# Sheet.net
KiCad netlist of a schematic drawn in Altium Designer
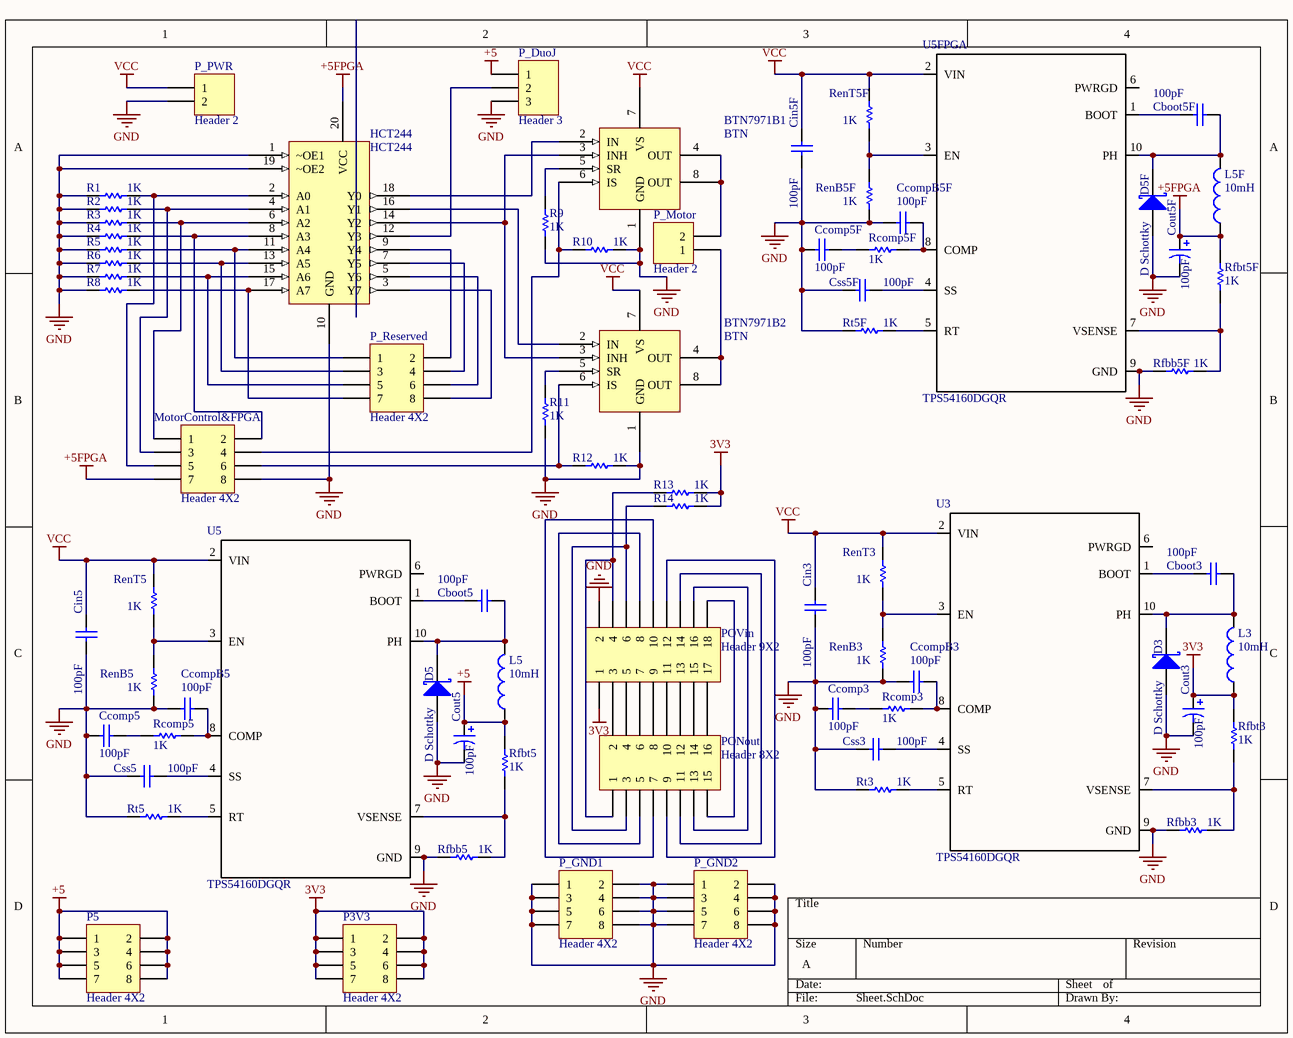
[diagram p0: Sheet.SchDoc]

(export (version "E")
  (design (tool "Eeschema 10.0.6"))
  (components
    (comp (ref "BTN7971B1")
      (value "BTN")
      (footprint "BTN7971B")
      (libsource (lib "2017-07-30_02-04-41") (part "BTN"))
    )
    (comp (ref "BTN7971B2")
      (value "BTN")
      (footprint "BTN7971B")
      (libsource (lib "2017-07-30_02-04-41") (part "BTN"))
    )
    (comp (ref "Cboot3")
      (value "100pF")
      (footprint "RAD-0.3")
      (description "Capacitor")
      (fields (field (name "Comment") "Cap") (field (name "PUBLISHER") "Altium Limited"))
      (libsource (lib "Miscellaneous Devices") (part "Cap"))
    )
    (comp (ref "Cboot5")
      (value "100pF")
      (footprint "RAD-0.3")
      (description "Capacitor")
      (fields (field (name "Comment") "Cap") (field (name "PUBLISHER") "Altium Limited"))
      (libsource (lib "Miscellaneous Devices") (part "Cap"))
    )
    (comp (ref "Cboot5F")
      (value "100pF")
      (footprint "RAD-0.3")
      (description "Capacitor")
      (fields (field (name "Comment") "Cap") (field (name "PUBLISHER") "Altium Limited"))
      (libsource (lib "Miscellaneous Devices") (part "Cap"))
    )
    (comp (ref "Ccomp3")
      (value "100pF")
      (footprint "RAD-0.3")
      (description "Capacitor")
      (fields (field (name "Comment") "Cap") (field (name "PUBLISHER") "Altium Limited"))
      (libsource (lib "Miscellaneous Devices") (part "Cap"))
    )
    (comp (ref "Ccomp5")
      (value "100pF")
      (footprint "RAD-0.3")
      (description "Capacitor")
      (fields (field (name "Comment") "Cap") (field (name "PUBLISHER") "Altium Limited"))
      (libsource (lib "Miscellaneous Devices") (part "Cap"))
    )
    (comp (ref "Ccomp5F")
      (value "100pF")
      (footprint "RAD-0.3")
      (description "Capacitor")
      (fields (field (name "Comment") "Cap") (field (name "PUBLISHER") "Altium Limited"))
      (libsource (lib "Miscellaneous Devices") (part "Cap"))
    )
    (comp (ref "CcompB3")
      (value "100pF")
      (footprint "RAD-0.3")
      (description "Capacitor")
      (fields (field (name "Comment") "Cap") (field (name "PUBLISHER") "Altium Limited"))
      (libsource (lib "Miscellaneous Devices") (part "Cap"))
    )
    (comp (ref "CcompB5")
      (value "100pF")
      (footprint "RAD-0.3")
      (description "Capacitor")
      (fields (field (name "Comment") "Cap") (field (name "PUBLISHER") "Altium Limited"))
      (libsource (lib "Miscellaneous Devices") (part "Cap"))
    )
    (comp (ref "CcompB5F")
      (value "100pF")
      (footprint "RAD-0.3")
      (description "Capacitor")
      (fields (field (name "Comment") "Cap") (field (name "PUBLISHER") "Altium Limited"))
      (libsource (lib "Miscellaneous Devices") (part "Cap"))
    )
    (comp (ref "Cin3")
      (value "100pF")
      (footprint "RAD-0.3")
      (description "Capacitor")
      (fields (field (name "Comment") "Cap") (field (name "PUBLISHER") "Altium Limited"))
      (libsource (lib "Miscellaneous Devices") (part "Cap"))
    )
    (comp (ref "Cin5")
      (value "100pF")
      (footprint "RAD-0.3")
      (description "Capacitor")
      (fields (field (name "Comment") "Cap") (field (name "PUBLISHER") "Altium Limited"))
      (libsource (lib "Miscellaneous Devices") (part "Cap"))
    )
    (comp (ref "Cin5F")
      (value "100pF")
      (footprint "RAD-0.3")
      (description "Capacitor")
      (fields (field (name "Comment") "Cap") (field (name "PUBLISHER") "Altium Limited"))
      (libsource (lib "Miscellaneous Devices") (part "Cap"))
    )
    (comp (ref "Cout3")
      (value "100pF")
      (footprint "RB7.6-15")
      (description "Polarized Capacitor (Radial)")
      (fields (field (name "Comment") "Cap Pol1") (field (name "PUBLISHER") "Altium Limited"))
      (libsource (lib "Miscellaneous Devices") (part "Cap Pol1"))
    )
    (comp (ref "Cout5")
      (value "100pF")
      (footprint "RB7.6-15")
      (description "Polarized Capacitor (Radial)")
      (fields (field (name "Comment") "Cap Pol1") (field (name "PUBLISHER") "Altium Limited"))
      (libsource (lib "Miscellaneous Devices") (part "Cap Pol1"))
    )
    (comp (ref "Cout5F")
      (value "100pF")
      (footprint "RB7.6-15")
      (description "Polarized Capacitor (Radial)")
      (fields (field (name "Comment") "Cap Pol1") (field (name "PUBLISHER") "Altium Limited"))
      (libsource (lib "Miscellaneous Devices") (part "Cap Pol1"))
    )
    (comp (ref "Css3")
      (value "100pF")
      (footprint "RAD-0.3")
      (description "Capacitor")
      (fields (field (name "Comment") "Cap") (field (name "PUBLISHER") "Altium Limited"))
      (libsource (lib "Miscellaneous Devices") (part "Cap"))
    )
    (comp (ref "Css5")
      (value "100pF")
      (footprint "RAD-0.3")
      (description "Capacitor")
      (fields (field (name "Comment") "Cap") (field (name "PUBLISHER") "Altium Limited"))
      (libsource (lib "Miscellaneous Devices") (part "Cap"))
    )
    (comp (ref "Css5F")
      (value "100pF")
      (footprint "RAD-0.3")
      (description "Capacitor")
      (fields (field (name "Comment") "Cap") (field (name "PUBLISHER") "Altium Limited"))
      (libsource (lib "Miscellaneous Devices") (part "Cap"))
    )
    (comp (ref "D3")
      (value "D Schottky")
      (footprint "SMB")
      (description "Schottky Diode")
      (fields (field (name "PUBLISHER") "Altium Limited"))
      (libsource (lib "Miscellaneous Devices") (part "D Schottky"))
    )
    (comp (ref "D5")
      (value "D Schottky")
      (footprint "SMB")
      (description "Schottky Diode")
      (fields (field (name "PUBLISHER") "Altium Limited"))
      (libsource (lib "Miscellaneous Devices") (part "D Schottky"))
    )
    (comp (ref "D5F")
      (value "D Schottky")
      (footprint "SMB")
      (description "Schottky Diode")
      (fields (field (name "PUBLISHER") "Altium Limited"))
      (libsource (lib "Miscellaneous Devices") (part "D Schottky"))
    )
    (comp (ref "HCT244")
      (value "HCT244")
      (footprint "DIP20")
      (libsource (lib "2017-07-30_02-04-41") (part "HCT244"))
    )
    (comp (ref "L3")
      (value "10mH")
      (footprint "0805")
      (description "Inductor")
      (fields (field (name "PUBLISHER") "Altium Limited"))
      (libsource (lib "Miscellaneous Devices") (part "Inductor"))
    )
    (comp (ref "L5")
      (value "10mH")
      (footprint "0805")
      (description "Inductor")
      (fields (field (name "PUBLISHER") "Altium Limited"))
      (libsource (lib "Miscellaneous Devices") (part "Inductor"))
    )
    (comp (ref "L5F")
      (value "10mH")
      (footprint "0805")
      (description "Inductor")
      (fields (field (name "PUBLISHER") "Altium Limited"))
      (libsource (lib "Miscellaneous Devices") (part "Inductor"))
    )
    (comp (ref "MotorControl&FPGA")
      (value "Header 4X2")
      (footprint "HDR2X4")
      (description "Header, 4-Pin, Dual row")
      (fields (field (name "PUBLISHER") "Altium Limited"))
      (libsource (lib "Miscellaneous Connectors") (part "Header 4X2"))
    )
    (comp (ref "P3V3")
      (value "Header 4X2")
      (footprint "HDR2X4")
      (description "Header, 4-Pin, Dual row")
      (fields (field (name "PUBLISHER") "Altium Limited"))
      (libsource (lib "Miscellaneous Connectors") (part "Header 4X2"))
    )
    (comp (ref "P5")
      (value "Header 4X2")
      (footprint "HDR2X4")
      (description "Header, 4-Pin, Dual row")
      (fields (field (name "PUBLISHER") "Altium Limited"))
      (libsource (lib "Miscellaneous Connectors") (part "Header 4X2"))
    )
    (comp (ref "PONout")
      (value "Header 8X2")
      (footprint "HDR2X8")
      (description "Header, 8-Pin, Dual row")
      (fields (field (name "PUBLISHER") "Altium Limited"))
      (libsource (lib "Miscellaneous Connectors") (part "Header 8X2"))
    )
    (comp (ref "POVin")
      (value "Header 9X2")
      (footprint "HDR2X9")
      (description "Header, 9-Pin, Dual row")
      (fields (field (name "PUBLISHER") "Altium Limited"))
      (libsource (lib "Miscellaneous Connectors") (part "Header 9X2"))
    )
    (comp (ref "P_DuoJ")
      (value "Header 3")
      (footprint "HDR1X3")
      (description "Header, 3-Pin")
      (fields (field (name "PUBLISHER") "Altium Limited"))
      (libsource (lib "Miscellaneous Connectors") (part "Header 3"))
    )
    (comp (ref "P_GND1")
      (value "Header 4X2")
      (footprint "HDR2X4")
      (description "Header, 4-Pin, Dual row")
      (fields (field (name "PUBLISHER") "Altium Limited"))
      (libsource (lib "Miscellaneous Connectors") (part "Header 4X2"))
    )
    (comp (ref "P_GND2")
      (value "Header 4X2")
      (footprint "HDR2X4")
      (description "Header, 4-Pin, Dual row")
      (fields (field (name "PUBLISHER") "Altium Limited"))
      (libsource (lib "Miscellaneous Connectors") (part "Header 4X2"))
    )
    (comp (ref "P_Motor")
      (value "Header 2")
      (footprint "HDR1X2")
      (description "Header, 2-Pin")
      (fields (field (name "PUBLISHER") "Altium Limited"))
      (libsource (lib "") (part "Header 2_1"))
    )
    (comp (ref "P_PWR")
      (value "Header 2")
      (footprint "HDR1X2")
      (description "Header, 2-Pin")
      (fields (field (name "PUBLISHER") "Altium Limited"))
      (libsource (lib "Miscellaneous Connectors") (part "Header 2"))
    )
    (comp (ref "P_Reserved")
      (value "Header 4X2")
      (footprint "HDR2X4")
      (description "Header, 4-Pin, Dual row")
      (fields (field (name "PUBLISHER") "Altium Limited"))
      (libsource (lib "Miscellaneous Connectors") (part "Header 4X2"))
    )
    (comp (ref "R1")
      (value "1K")
      (footprint "AXIAL-0.3")
      (description "Resistor")
      (fields (field (name "Comment") "Res1") (field (name "PUBLISHER") "Altium Limited"))
      (libsource (lib "Miscellaneous Devices") (part "Res1"))
    )
    (comp (ref "R2")
      (value "1K")
      (footprint "AXIAL-0.3")
      (description "Resistor")
      (fields (field (name "Comment") "Res1") (field (name "PUBLISHER") "Altium Limited"))
      (libsource (lib "Miscellaneous Devices") (part "Res1"))
    )
    (comp (ref "R3")
      (value "1K")
      (footprint "AXIAL-0.3")
      (description "Resistor")
      (fields (field (name "Comment") "Res1") (field (name "PUBLISHER") "Altium Limited"))
      (libsource (lib "Miscellaneous Devices") (part "Res1"))
    )
    (comp (ref "R4")
      (value "1K")
      (footprint "AXIAL-0.3")
      (description "Resistor")
      (fields (field (name "Comment") "Res1") (field (name "PUBLISHER") "Altium Limited"))
      (libsource (lib "Miscellaneous Devices") (part "Res1"))
    )
    (comp (ref "R5")
      (value "1K")
      (footprint "AXIAL-0.3")
      (description "Resistor")
      (fields (field (name "Comment") "Res1") (field (name "PUBLISHER") "Altium Limited"))
      (libsource (lib "Miscellaneous Devices") (part "Res1"))
    )
    (comp (ref "R6")
      (value "1K")
      (footprint "AXIAL-0.3")
      (description "Resistor")
      (fields (field (name "Comment") "Res1") (field (name "PUBLISHER") "Altium Limited"))
      (libsource (lib "Miscellaneous Devices") (part "Res1"))
    )
    (comp (ref "R7")
      (value "1K")
      (footprint "AXIAL-0.3")
      (description "Resistor")
      (fields (field (name "Comment") "Res1") (field (name "PUBLISHER") "Altium Limited"))
      (libsource (lib "Miscellaneous Devices") (part "Res1"))
    )
    (comp (ref "R8")
      (value "1K")
      (footprint "AXIAL-0.3")
      (description "Resistor")
      (fields (field (name "Comment") "Res1") (field (name "PUBLISHER") "Altium Limited"))
      (libsource (lib "Miscellaneous Devices") (part "Res1"))
    )
    (comp (ref "R9")
      (value "1K")
      (footprint "AXIAL-0.3")
      (description "Resistor")
      (fields (field (name "Comment") "Res1") (field (name "PUBLISHER") "Altium Limited"))
      (libsource (lib "Miscellaneous Devices") (part "Res1"))
    )
    (comp (ref "R10")
      (value "1K")
      (footprint "AXIAL-0.3")
      (description "Resistor")
      (fields (field (name "Comment") "Res1") (field (name "PUBLISHER") "Altium Limited"))
      (libsource (lib "Miscellaneous Devices") (part "Res1"))
    )
    (comp (ref "R11")
      (value "1K")
      (footprint "AXIAL-0.3")
      (description "Resistor")
      (fields (field (name "Comment") "Res1") (field (name "PUBLISHER") "Altium Limited"))
      (libsource (lib "Miscellaneous Devices") (part "Res1"))
    )
    (comp (ref "R12")
      (value "1K")
      (footprint "AXIAL-0.3")
      (description "Resistor")
      (fields (field (name "Comment") "Res1") (field (name "PUBLISHER") "Altium Limited"))
      (libsource (lib "Miscellaneous Devices") (part "Res1"))
    )
    (comp (ref "R13")
      (value "1K")
      (footprint "AXIAL-0.3")
      (description "Resistor")
      (fields (field (name "Comment") "Res1") (field (name "PUBLISHER") "Altium Limited"))
      (libsource (lib "Miscellaneous Devices") (part "Res1"))
    )
    (comp (ref "R14")
      (value "1K")
      (footprint "AXIAL-0.3")
      (description "Resistor")
      (fields (field (name "Comment") "Res1") (field (name "PUBLISHER") "Altium Limited"))
      (libsource (lib "Miscellaneous Devices") (part "Res1"))
    )
    (comp (ref "Rcomp3")
      (value "1K")
      (footprint "AXIAL-0.3")
      (description "Resistor")
      (fields (field (name "Comment") "Res1") (field (name "PUBLISHER") "Altium Limited"))
      (libsource (lib "Miscellaneous Devices") (part "Res1"))
    )
    (comp (ref "Rcomp5")
      (value "1K")
      (footprint "AXIAL-0.3")
      (description "Resistor")
      (fields (field (name "Comment") "Res1") (field (name "PUBLISHER") "Altium Limited"))
      (libsource (lib "Miscellaneous Devices") (part "Res1"))
    )
    (comp (ref "Rcomp5F")
      (value "1K")
      (footprint "AXIAL-0.3")
      (description "Resistor")
      (fields (field (name "Comment") "Res1") (field (name "PUBLISHER") "Altium Limited"))
      (libsource (lib "Miscellaneous Devices") (part "Res1"))
    )
    (comp (ref "RenB3")
      (value "1K")
      (footprint "AXIAL-0.3")
      (description "Resistor")
      (fields (field (name "Comment") "Res1") (field (name "PUBLISHER") "Altium Limited"))
      (libsource (lib "Miscellaneous Devices") (part "Res1"))
    )
    (comp (ref "RenB5")
      (value "1K")
      (footprint "AXIAL-0.3")
      (description "Resistor")
      (fields (field (name "Comment") "Res1") (field (name "PUBLISHER") "Altium Limited"))
      (libsource (lib "Miscellaneous Devices") (part "Res1"))
    )
    (comp (ref "RenB5F")
      (value "1K")
      (footprint "AXIAL-0.3")
      (description "Resistor")
      (fields (field (name "Comment") "Res1") (field (name "PUBLISHER") "Altium Limited"))
      (libsource (lib "Miscellaneous Devices") (part "Res1"))
    )
    (comp (ref "RenT3")
      (value "1K")
      (footprint "AXIAL-0.3")
      (description "Resistor")
      (fields (field (name "Comment") "Res1") (field (name "PUBLISHER") "Altium Limited"))
      (libsource (lib "Miscellaneous Devices") (part "Res1"))
    )
    (comp (ref "RenT5")
      (value "1K")
      (footprint "AXIAL-0.3")
      (description "Resistor")
      (fields (field (name "Comment") "Res1") (field (name "PUBLISHER") "Altium Limited"))
      (libsource (lib "Miscellaneous Devices") (part "Res1"))
    )
    (comp (ref "RenT5F")
      (value "1K")
      (footprint "AXIAL-0.3")
      (description "Resistor")
      (fields (field (name "Comment") "Res1") (field (name "PUBLISHER") "Altium Limited"))
      (libsource (lib "Miscellaneous Devices") (part "Res1"))
    )
    (comp (ref "Rfbb3")
      (value "1K")
      (footprint "AXIAL-0.3")
      (description "Resistor")
      (fields (field (name "Comment") "Res1") (field (name "PUBLISHER") "Altium Limited"))
      (libsource (lib "Miscellaneous Devices") (part "Res1"))
    )
    (comp (ref "Rfbb5")
      (value "1K")
      (footprint "AXIAL-0.3")
      (description "Resistor")
      (fields (field (name "Comment") "Res1") (field (name "PUBLISHER") "Altium Limited"))
      (libsource (lib "Miscellaneous Devices") (part "Res1"))
    )
    (comp (ref "Rfbb5F")
      (value "1K")
      (footprint "AXIAL-0.3")
      (description "Resistor")
      (fields (field (name "Comment") "Res1") (field (name "PUBLISHER") "Altium Limited"))
      (libsource (lib "Miscellaneous Devices") (part "Res1"))
    )
    (comp (ref "Rfbt3")
      (value "1K")
      (footprint "AXIAL-0.3")
      (description "Resistor")
      (fields (field (name "Comment") "Res1") (field (name "PUBLISHER") "Altium Limited"))
      (libsource (lib "Miscellaneous Devices") (part "Res1"))
    )
    (comp (ref "Rfbt5")
      (value "1K")
      (footprint "AXIAL-0.3")
      (description "Resistor")
      (fields (field (name "Comment") "Res1") (field (name "PUBLISHER") "Altium Limited"))
      (libsource (lib "Miscellaneous Devices") (part "Res1"))
    )
    (comp (ref "Rfbt5F")
      (value "1K")
      (footprint "AXIAL-0.3")
      (description "Resistor")
      (fields (field (name "Comment") "Res1") (field (name "PUBLISHER") "Altium Limited"))
      (libsource (lib "Miscellaneous Devices") (part "Res1"))
    )
    (comp (ref "Rt3")
      (value "1K")
      (footprint "AXIAL-0.3")
      (description "Resistor")
      (fields (field (name "Comment") "Res1") (field (name "PUBLISHER") "Altium Limited"))
      (libsource (lib "Miscellaneous Devices") (part "Res1"))
    )
    (comp (ref "Rt5")
      (value "1K")
      (footprint "AXIAL-0.3")
      (description "Resistor")
      (fields (field (name "Comment") "Res1") (field (name "PUBLISHER") "Altium Limited"))
      (libsource (lib "Miscellaneous Devices") (part "Res1"))
    )
    (comp (ref "Rt5F")
      (value "1K")
      (footprint "AXIAL-0.3")
      (description "Resistor")
      (fields (field (name "Comment") "Res1") (field (name "PUBLISHER") "Altium Limited"))
      (libsource (lib "Miscellaneous Devices") (part "Res1"))
    )
    (comp (ref "U3")
      (value "TPS54160DGQR")
      (footprint "S-PDSO-G10")
      (description "Imported")
      (fields (field (name "MANUFACTURER_PART_NUMBER") "TPS54140DGQR"))
      (libsource (lib "2017-07-30_02-04-41") (part "TPS54160DGQR"))
    )
    (comp (ref "U5")
      (value "TPS54160DGQR")
      (footprint "S-PDSO-G10")
      (description "Imported")
      (fields (field (name "MANUFACTURER_PART_NUMBER") "TPS54140DGQR"))
      (libsource (lib "2017-07-30_02-04-41") (part "TPS54160DGQR"))
    )
    (comp (ref "U5FPGA")
      (value "TPS54160DGQR")
      (footprint "S-PDSO-G10")
      (description "Imported")
      (fields (field (name "MANUFACTURER_PART_NUMBER") "TPS54140DGQR"))
      (libsource (lib "2017-07-30_02-04-41") (part "TPS54160DGQR"))
    )
  )
  (nets
    (net (code "1") (name "+5") (class "Default")
      (node (ref "Cout5") (pin "1") (pinfunction "1_1") (pintype "passive"))
      (node (ref "L5") (pin "1") (pinfunction "1_1") (pintype "passive"))
      (node (ref "P5") (pin "1") (pinfunction "1_1") (pintype "passive"))
      (node (ref "P5") (pin "2") (pinfunction "2_2") (pintype "passive"))
      (node (ref "P5") (pin "3") (pinfunction "3_3") (pintype "passive"))
      (node (ref "P5") (pin "4") (pinfunction "4_4") (pintype "passive"))
      (node (ref "P5") (pin "5") (pinfunction "5_5") (pintype "passive"))
      (node (ref "P5") (pin "6") (pinfunction "6_6") (pintype "passive"))
      (node (ref "P5") (pin "7") (pinfunction "7_7") (pintype "passive"))
      (node (ref "P5") (pin "8") (pinfunction "8_8") (pintype "passive"))
      (node (ref "P_DuoJ") (pin "1") (pinfunction "1_1") (pintype "passive"))
      (node (ref "Rfbt5") (pin "2") (pinfunction "2_2") (pintype "passive"))
    )
    (net (code "2") (name "+5FPGA") (class "Default")
      (node (ref "Cout5F") (pin "1") (pinfunction "1_1") (pintype "passive"))
      (node (ref "HCT244") (pin "20") (pinfunction "VCC_20") (pintype "power_in"))
      (node (ref "L5F") (pin "1") (pinfunction "1_1") (pintype "passive"))
      (node (ref "MotorControl&FPGA") (pin "7") (pinfunction "7_7") (pintype "passive"))
      (node (ref "Rfbt5F") (pin "2") (pinfunction "2_2") (pintype "passive"))
    )
    (net (code "3") (name "3V3") (class "Default")
      (node (ref "Cout3") (pin "1") (pinfunction "1_1") (pintype "passive"))
      (node (ref "L3") (pin "1") (pinfunction "1_1") (pintype "passive"))
      (node (ref "P3V3") (pin "1") (pinfunction "1_1") (pintype "passive"))
      (node (ref "P3V3") (pin "2") (pinfunction "2_2") (pintype "passive"))
      (node (ref "P3V3") (pin "3") (pinfunction "3_3") (pintype "passive"))
      (node (ref "P3V3") (pin "4") (pinfunction "4_4") (pintype "passive"))
      (node (ref "P3V3") (pin "5") (pinfunction "5_5") (pintype "passive"))
      (node (ref "P3V3") (pin "6") (pinfunction "6_6") (pintype "passive"))
      (node (ref "P3V3") (pin "7") (pinfunction "7_7") (pintype "passive"))
      (node (ref "P3V3") (pin "8") (pinfunction "8_8") (pintype "passive"))
      (node (ref "POVin") (pin "1") (pinfunction "1_1") (pintype "passive"))
      (node (ref "R13") (pin "2") (pinfunction "2_2") (pintype "passive"))
      (node (ref "R14") (pin "2") (pinfunction "2_2") (pintype "passive"))
      (node (ref "Rfbt3") (pin "2") (pinfunction "2_2") (pintype "passive"))
    )
    (net (code "4") (name "GND") (class "Default")
      (node (ref "BTN7971B1") (pin "1") (pinfunction "GND_1") (pintype "power_in"))
      (node (ref "BTN7971B2") (pin "1") (pinfunction "GND_1") (pintype "power_in"))
      (node (ref "Ccomp3") (pin "2") (pinfunction "2_2") (pintype "passive"))
      (node (ref "Ccomp5") (pin "2") (pinfunction "2_2") (pintype "passive"))
      (node (ref "Ccomp5F") (pin "2") (pinfunction "2_2") (pintype "passive"))
      (node (ref "CcompB3") (pin "1") (pinfunction "1_1") (pintype "passive"))
      (node (ref "CcompB5") (pin "1") (pinfunction "1_1") (pintype "passive"))
      (node (ref "CcompB5F") (pin "1") (pinfunction "1_1") (pintype "passive"))
      (node (ref "Cin3") (pin "1") (pinfunction "1_1") (pintype "passive"))
      (node (ref "Cin5") (pin "1") (pinfunction "1_1") (pintype "passive"))
      (node (ref "Cin5F") (pin "1") (pinfunction "1_1") (pintype "passive"))
      (node (ref "Cout3") (pin "2") (pinfunction "2_2") (pintype "passive"))
      (node (ref "Cout5") (pin "2") (pinfunction "2_2") (pintype "passive"))
      (node (ref "Cout5F") (pin "2") (pinfunction "2_2") (pintype "passive"))
      (node (ref "Css3") (pin "1") (pinfunction "1_1") (pintype "passive"))
      (node (ref "Css5") (pin "1") (pinfunction "1_1") (pintype "passive"))
      (node (ref "Css5F") (pin "1") (pinfunction "1_1") (pintype "passive"))
      (node (ref "D3") (pin "1") (pinfunction "A_1") (pintype "passive"))
      (node (ref "D5") (pin "1") (pinfunction "A_1") (pintype "passive"))
      (node (ref "D5F") (pin "1") (pinfunction "A_1") (pintype "passive"))
      (node (ref "HCT244") (pin "1") (pinfunction "~OE1_1") (pintype "input"))
      (node (ref "HCT244") (pin "10") (pinfunction "GND_10") (pintype "power_in"))
      (node (ref "HCT244") (pin "19") (pinfunction "~OE2_19") (pintype "input"))
      (node (ref "MotorControl&FPGA") (pin "8") (pinfunction "8_8") (pintype "passive"))
      (node (ref "POVin") (pin "2") (pinfunction "2_2") (pintype "passive"))
      (node (ref "P_DuoJ") (pin "3") (pinfunction "3_3") (pintype "passive"))
      (node (ref "P_GND1") (pin "1") (pinfunction "1_1") (pintype "passive"))
      (node (ref "P_GND1") (pin "2") (pinfunction "2_2") (pintype "passive"))
      (node (ref "P_GND1") (pin "3") (pinfunction "3_3") (pintype "passive"))
      (node (ref "P_GND1") (pin "4") (pinfunction "4_4") (pintype "passive"))
      (node (ref "P_GND1") (pin "5") (pinfunction "5_5") (pintype "passive"))
      (node (ref "P_GND1") (pin "6") (pinfunction "6_6") (pintype "passive"))
      (node (ref "P_GND1") (pin "7") (pinfunction "7_7") (pintype "passive"))
      (node (ref "P_GND1") (pin "8") (pinfunction "8_8") (pintype "passive"))
      (node (ref "P_GND2") (pin "1") (pinfunction "1_1") (pintype "passive"))
      (node (ref "P_GND2") (pin "2") (pinfunction "2_2") (pintype "passive"))
      (node (ref "P_GND2") (pin "3") (pinfunction "3_3") (pintype "passive"))
      (node (ref "P_GND2") (pin "4") (pinfunction "4_4") (pintype "passive"))
      (node (ref "P_GND2") (pin "5") (pinfunction "5_5") (pintype "passive"))
      (node (ref "P_GND2") (pin "6") (pinfunction "6_6") (pintype "passive"))
      (node (ref "P_GND2") (pin "7") (pinfunction "7_7") (pintype "passive"))
      (node (ref "P_GND2") (pin "8") (pinfunction "8_8") (pintype "passive"))
      (node (ref "P_PWR") (pin "2") (pinfunction "2_2") (pintype "passive"))
      (node (ref "R1") (pin "1") (pinfunction "1_1") (pintype "passive"))
      (node (ref "R10") (pin "2") (pinfunction "2_2") (pintype "passive"))
      (node (ref "R11") (pin "1") (pinfunction "1_1") (pintype "passive"))
      (node (ref "R12") (pin "2") (pinfunction "2_2") (pintype "passive"))
      (node (ref "R2") (pin "1") (pinfunction "1_1") (pintype "passive"))
      (node (ref "R3") (pin "1") (pinfunction "1_1") (pintype "passive"))
      (node (ref "R4") (pin "1") (pinfunction "1_1") (pintype "passive"))
      (node (ref "R5") (pin "1") (pinfunction "1_1") (pintype "passive"))
      (node (ref "R6") (pin "1") (pinfunction "1_1") (pintype "passive"))
      (node (ref "R7") (pin "1") (pinfunction "1_1") (pintype "passive"))
      (node (ref "R8") (pin "1") (pinfunction "1_1") (pintype "passive"))
      (node (ref "R9") (pin "1") (pinfunction "1_1") (pintype "passive"))
      (node (ref "RenB3") (pin "1") (pinfunction "1_1") (pintype "passive"))
      (node (ref "RenB5") (pin "1") (pinfunction "1_1") (pintype "passive"))
      (node (ref "RenB5F") (pin "1") (pinfunction "1_1") (pintype "passive"))
      (node (ref "Rfbb3") (pin "1") (pinfunction "1_1") (pintype "passive"))
      (node (ref "Rfbb5") (pin "1") (pinfunction "1_1") (pintype "passive"))
      (node (ref "Rfbb5F") (pin "1") (pinfunction "1_1") (pintype "passive"))
      (node (ref "Rt3") (pin "1") (pinfunction "1_1") (pintype "passive"))
      (node (ref "Rt5") (pin "1") (pinfunction "1_1") (pintype "passive"))
      (node (ref "Rt5F") (pin "1") (pinfunction "1_1") (pintype "passive"))
      (node (ref "U3") (pin "11") (pinfunction "GND_11") (pintype "passive"))
      (node (ref "U3") (pin "9") (pinfunction "GND_9") (pintype "passive"))
      (node (ref "U5") (pin "11") (pinfunction "GND_11") (pintype "passive"))
      (node (ref "U5") (pin "9") (pinfunction "GND_9") (pintype "passive"))
      (node (ref "U5FPGA") (pin "11") (pinfunction "GND_11") (pintype "passive"))
      (node (ref "U5FPGA") (pin "9") (pinfunction "GND_9") (pintype "passive"))
    )
    (net (code "5") (name "Net-(BTN7971B1-IN)") (class "Default")
      (node (ref "BTN7971B1") (pin "2") (pinfunction "IN_2") (pintype "input"))
      (node (ref "HCT244") (pin "18") (pinfunction "Y0_18") (pintype "output"))
    )
    (net (code "6") (name "Net-(BTN7971B1-INH)") (class "Default")
      (node (ref "BTN7971B1") (pin "3") (pinfunction "INH_3") (pintype "input"))
      (node (ref "BTN7971B2") (pin "3") (pinfunction "INH_3") (pintype "input"))
      (node (ref "HCT244") (pin "14") (pinfunction "Y2_14") (pintype "output"))
    )
    (net (code "7") (name "Net-(BTN7971B1-IS)") (class "Default")
      (node (ref "BTN7971B1") (pin "6") (pinfunction "IS_6") (pintype "input"))
      (node (ref "MotorControl&FPGA") (pin "4") (pinfunction "4_4") (pintype "passive"))
      (node (ref "R10") (pin "1") (pinfunction "1_1") (pintype "passive"))
    )
    (net (code "8") (name "Net-(BTN7971B1-OUT-Pad4)") (class "Default")
      (node (ref "BTN7971B1") (pin "4") (pinfunction "OUT_4") (pintype "open_collector"))
      (node (ref "BTN7971B1") (pin "8") (pinfunction "OUT_8") (pintype "open_collector"))
      (node (ref "P_Motor") (pin "2") (pinfunction "2_2") (pintype "passive"))
    )
    (net (code "9") (name "Net-(BTN7971B1-SR)") (class "Default")
      (node (ref "BTN7971B1") (pin "5") (pinfunction "SR_5") (pintype "input"))
      (node (ref "R9") (pin "2") (pinfunction "2_2") (pintype "passive"))
    )
    (net (code "10") (name "Net-(BTN7971B2-IN)") (class "Default")
      (node (ref "BTN7971B2") (pin "2") (pinfunction "IN_2") (pintype "input"))
      (node (ref "HCT244") (pin "16") (pinfunction "Y1_16") (pintype "output"))
    )
    (net (code "11") (name "Net-(BTN7971B2-IS)") (class "Default")
      (node (ref "BTN7971B2") (pin "6") (pinfunction "IS_6") (pintype "input"))
      (node (ref "MotorControl&FPGA") (pin "6") (pinfunction "6_6") (pintype "passive"))
      (node (ref "R12") (pin "1") (pinfunction "1_1") (pintype "passive"))
    )
    (net (code "12") (name "Net-(BTN7971B2-OUT-Pad4)") (class "Default")
      (node (ref "BTN7971B2") (pin "4") (pinfunction "OUT_4") (pintype "open_collector"))
      (node (ref "BTN7971B2") (pin "8") (pinfunction "OUT_8") (pintype "open_collector"))
      (node (ref "P_Motor") (pin "1") (pinfunction "1_1") (pintype "passive"))
    )
    (net (code "13") (name "Net-(BTN7971B2-SR)") (class "Default")
      (node (ref "BTN7971B2") (pin "5") (pinfunction "SR_5") (pintype "input"))
      (node (ref "R11") (pin "2") (pinfunction "2_2") (pintype "passive"))
    )
    (net (code "14") (name "Net-(Ccomp3-Pad1)") (class "Default")
      (node (ref "Ccomp3") (pin "1") (pinfunction "1_1") (pintype "passive"))
      (node (ref "Rcomp3") (pin "2") (pinfunction "2_2") (pintype "passive"))
    )
    (net (code "15") (name "Net-(Ccomp5-Pad1)") (class "Default")
      (node (ref "Ccomp5") (pin "1") (pinfunction "1_1") (pintype "passive"))
      (node (ref "Rcomp5") (pin "2") (pinfunction "2_2") (pintype "passive"))
    )
    (net (code "16") (name "Net-(Ccomp5F-Pad1)") (class "Default")
      (node (ref "Ccomp5F") (pin "1") (pinfunction "1_1") (pintype "passive"))
      (node (ref "Rcomp5F") (pin "2") (pinfunction "2_2") (pintype "passive"))
    )
    (net (code "17") (name "Net-(D3-K)") (class "Default")
      (node (ref "Cboot3") (pin "2") (pinfunction "2_2") (pintype "passive"))
      (node (ref "D3") (pin "2") (pinfunction "K_2") (pintype "passive"))
      (node (ref "L3") (pin "2") (pinfunction "2_2") (pintype "passive"))
      (node (ref "U3") (pin "10") (pinfunction "PH_10") (pintype "passive"))
    )
    (net (code "18") (name "Net-(D5-K)") (class "Default")
      (node (ref "Cboot5") (pin "2") (pinfunction "2_2") (pintype "passive"))
      (node (ref "D5") (pin "2") (pinfunction "K_2") (pintype "passive"))
      (node (ref "L5") (pin "2") (pinfunction "2_2") (pintype "passive"))
      (node (ref "U5") (pin "10") (pinfunction "PH_10") (pintype "passive"))
    )
    (net (code "19") (name "Net-(D5F-K)") (class "Default")
      (node (ref "Cboot5F") (pin "2") (pinfunction "2_2") (pintype "passive"))
      (node (ref "D5F") (pin "2") (pinfunction "K_2") (pintype "passive"))
      (node (ref "L5F") (pin "2") (pinfunction "2_2") (pintype "passive"))
      (node (ref "U5FPGA") (pin "10") (pinfunction "PH_10") (pintype "passive"))
    )
    (net (code "20") (name "Net-(HCT244-A0)") (class "Default")
      (node (ref "HCT244") (pin "2") (pinfunction "A0_2") (pintype "input"))
      (node (ref "MotorControl&FPGA") (pin "5") (pinfunction "5_5") (pintype "passive"))
      (node (ref "R1") (pin "2") (pinfunction "2_2") (pintype "passive"))
    )
    (net (code "21") (name "Net-(HCT244-A1)") (class "Default")
      (node (ref "HCT244") (pin "4") (pinfunction "A1_4") (pintype "input"))
      (node (ref "MotorControl&FPGA") (pin "3") (pinfunction "3_3") (pintype "passive"))
      (node (ref "R2") (pin "2") (pinfunction "2_2") (pintype "passive"))
    )
    (net (code "22") (name "Net-(HCT244-A2)") (class "Default")
      (node (ref "HCT244") (pin "6") (pinfunction "A2_6") (pintype "input"))
      (node (ref "MotorControl&FPGA") (pin "1") (pinfunction "1_1") (pintype "passive"))
      (node (ref "R3") (pin "2") (pinfunction "2_2") (pintype "passive"))
    )
    (net (code "23") (name "Net-(HCT244-A3)") (class "Default")
      (node (ref "HCT244") (pin "8") (pinfunction "A3_8") (pintype "input"))
      (node (ref "MotorControl&FPGA") (pin "2") (pinfunction "2_2") (pintype "passive"))
      (node (ref "R4") (pin "2") (pinfunction "2_2") (pintype "passive"))
    )
    (net (code "24") (name "Net-(HCT244-A4)") (class "Default")
      (node (ref "HCT244") (pin "11") (pinfunction "A4_11") (pintype "input"))
      (node (ref "P_Reserved") (pin "1") (pinfunction "1_1") (pintype "passive"))
      (node (ref "R5") (pin "2") (pinfunction "2_2") (pintype "passive"))
    )
    (net (code "25") (name "Net-(HCT244-A5)") (class "Default")
      (node (ref "HCT244") (pin "13") (pinfunction "A5_13") (pintype "input"))
      (node (ref "P_Reserved") (pin "3") (pinfunction "3_3") (pintype "passive"))
      (node (ref "R6") (pin "2") (pinfunction "2_2") (pintype "passive"))
    )
    (net (code "26") (name "Net-(HCT244-A6)") (class "Default")
      (node (ref "HCT244") (pin "15") (pinfunction "A6_15") (pintype "input"))
      (node (ref "P_Reserved") (pin "5") (pinfunction "5_5") (pintype "passive"))
      (node (ref "R7") (pin "2") (pinfunction "2_2") (pintype "passive"))
    )
    (net (code "27") (name "Net-(HCT244-A7)") (class "Default")
      (node (ref "HCT244") (pin "17") (pinfunction "A7_17") (pintype "input"))
      (node (ref "P_Reserved") (pin "7") (pinfunction "7_7") (pintype "passive"))
      (node (ref "R8") (pin "2") (pinfunction "2_2") (pintype "passive"))
    )
    (net (code "28") (name "Net-(HCT244-Y3)") (class "Default")
      (node (ref "HCT244") (pin "12") (pinfunction "Y3_12") (pintype "output"))
      (node (ref "P_DuoJ") (pin "2") (pinfunction "2_2") (pintype "passive"))
    )
    (net (code "29") (name "Net-(HCT244-Y4)") (class "Default")
      (node (ref "HCT244") (pin "9") (pinfunction "Y4_9") (pintype "output"))
      (node (ref "P_Reserved") (pin "2") (pinfunction "2_2") (pintype "passive"))
    )
    (net (code "30") (name "Net-(HCT244-Y5)") (class "Default")
      (node (ref "HCT244") (pin "7") (pinfunction "Y5_7") (pintype "output"))
      (node (ref "P_Reserved") (pin "4") (pinfunction "4_4") (pintype "passive"))
    )
    (net (code "31") (name "Net-(HCT244-Y6)") (class "Default")
      (node (ref "HCT244") (pin "5") (pinfunction "Y6_5") (pintype "output"))
      (node (ref "P_Reserved") (pin "6") (pinfunction "6_6") (pintype "passive"))
    )
    (net (code "32") (name "Net-(HCT244-Y7)") (class "Default")
      (node (ref "HCT244") (pin "3") (pinfunction "Y7_3") (pintype "output"))
      (node (ref "P_Reserved") (pin "8") (pinfunction "8_8") (pintype "passive"))
    )
    (net (code "33") (name "Net-(PONout-Pad1)") (class "Default")
      (node (ref "PONout") (pin "1") (pinfunction "1_1") (pintype "passive"))
      (node (ref "POVin") (pin "4") (pinfunction "4_4") (pintype "passive"))
      (node (ref "R13") (pin "1") (pinfunction "1_1") (pintype "passive"))
    )
    (net (code "34") (name "Net-(PONout-Pad2)") (class "Default")
      (node (ref "PONout") (pin "2") (pinfunction "2_2") (pintype "passive"))
      (node (ref "POVin") (pin "3") (pinfunction "3_3") (pintype "passive"))
    )
    (net (code "35") (name "Net-(PONout-Pad3)") (class "Default")
      (node (ref "PONout") (pin "3") (pinfunction "3_3") (pintype "passive"))
      (node (ref "POVin") (pin "6") (pinfunction "6_6") (pintype "passive"))
      (node (ref "R14") (pin "1") (pinfunction "1_1") (pintype "passive"))
    )
    (net (code "36") (name "Net-(PONout-Pad4)") (class "Default")
      (node (ref "PONout") (pin "4") (pinfunction "4_4") (pintype "passive"))
      (node (ref "POVin") (pin "5") (pinfunction "5_5") (pintype "passive"))
    )
    (net (code "37") (name "Net-(PONout-Pad5)") (class "Default")
      (node (ref "PONout") (pin "5") (pinfunction "5_5") (pintype "passive"))
      (node (ref "POVin") (pin "8") (pinfunction "8_8") (pintype "passive"))
    )
    (net (code "38") (name "Net-(PONout-Pad6)") (class "Default")
      (node (ref "PONout") (pin "6") (pinfunction "6_6") (pintype "passive"))
      (node (ref "POVin") (pin "7") (pinfunction "7_7") (pintype "passive"))
    )
    (net (code "39") (name "Net-(PONout-Pad7)") (class "Default")
      (node (ref "PONout") (pin "7") (pinfunction "7_7") (pintype "passive"))
      (node (ref "POVin") (pin "10") (pinfunction "10_10") (pintype "passive"))
    )
    (net (code "40") (name "Net-(PONout-Pad8)") (class "Default")
      (node (ref "PONout") (pin "8") (pinfunction "8_8") (pintype "passive"))
      (node (ref "POVin") (pin "9") (pinfunction "9_9") (pintype "passive"))
    )
    (net (code "41") (name "Net-(PONout-Pad9)") (class "Default")
      (node (ref "PONout") (pin "9") (pinfunction "9_9") (pintype "passive"))
      (node (ref "POVin") (pin "12") (pinfunction "12_12") (pintype "passive"))
    )
    (net (code "42") (name "Net-(PONout-Pad10)") (class "Default")
      (node (ref "PONout") (pin "10") (pinfunction "10_10") (pintype "passive"))
      (node (ref "POVin") (pin "11") (pinfunction "11_11") (pintype "passive"))
    )
    (net (code "43") (name "Net-(PONout-Pad11)") (class "Default")
      (node (ref "PONout") (pin "11") (pinfunction "11_11") (pintype "passive"))
      (node (ref "POVin") (pin "14") (pinfunction "14_14") (pintype "passive"))
    )
    (net (code "44") (name "Net-(PONout-Pad12)") (class "Default")
      (node (ref "PONout") (pin "12") (pinfunction "12_12") (pintype "passive"))
      (node (ref "POVin") (pin "13") (pinfunction "13_13") (pintype "passive"))
    )
    (net (code "45") (name "Net-(PONout-Pad13)") (class "Default")
      (node (ref "PONout") (pin "13") (pinfunction "13_13") (pintype "passive"))
      (node (ref "POVin") (pin "16") (pinfunction "16_16") (pintype "passive"))
    )
    (net (code "46") (name "Net-(PONout-Pad14)") (class "Default")
      (node (ref "PONout") (pin "14") (pinfunction "14_14") (pintype "passive"))
      (node (ref "POVin") (pin "15") (pinfunction "15_15") (pintype "passive"))
    )
    (net (code "47") (name "Net-(PONout-Pad15)") (class "Default")
      (node (ref "PONout") (pin "15") (pinfunction "15_15") (pintype "passive"))
      (node (ref "POVin") (pin "18") (pinfunction "18_18") (pintype "passive"))
    )
    (net (code "48") (name "Net-(PONout-Pad16)") (class "Default")
      (node (ref "PONout") (pin "16") (pinfunction "16_16") (pintype "passive"))
      (node (ref "POVin") (pin "17") (pinfunction "17_17") (pintype "passive"))
    )
    (net (code "49") (name "Net-(U3-BOOT)") (class "Default")
      (node (ref "Cboot3") (pin "1") (pinfunction "1_1") (pintype "passive"))
      (node (ref "U3") (pin "1") (pinfunction "BOOT_1") (pintype "passive"))
    )
    (net (code "50") (name "Net-(U3-COMP)") (class "Default")
      (node (ref "CcompB3") (pin "2") (pinfunction "2_2") (pintype "passive"))
      (node (ref "Rcomp3") (pin "1") (pinfunction "1_1") (pintype "passive"))
      (node (ref "U3") (pin "8") (pinfunction "COMP_8") (pintype "passive"))
    )
    (net (code "51") (name "Net-(U3-EN)") (class "Default")
      (node (ref "RenB3") (pin "2") (pinfunction "2_2") (pintype "passive"))
      (node (ref "RenT3") (pin "1") (pinfunction "1_1") (pintype "passive"))
      (node (ref "U3") (pin "3") (pinfunction "EN_3") (pintype "passive"))
    )
    (net (code "52") (name "Net-(U3-RT)") (class "Default")
      (node (ref "Rt3") (pin "2") (pinfunction "2_2") (pintype "passive"))
      (node (ref "U3") (pin "5") (pinfunction "RT_5") (pintype "passive"))
    )
    (net (code "53") (name "Net-(U3-SS)") (class "Default")
      (node (ref "Css3") (pin "2") (pinfunction "2_2") (pintype "passive"))
      (node (ref "U3") (pin "4") (pinfunction "SS_4") (pintype "passive"))
    )
    (net (code "54") (name "Net-(U3-VSENSE)") (class "Default")
      (node (ref "Rfbb3") (pin "2") (pinfunction "2_2") (pintype "passive"))
      (node (ref "Rfbt3") (pin "1") (pinfunction "1_1") (pintype "passive"))
      (node (ref "U3") (pin "7") (pinfunction "VSENSE_7") (pintype "passive"))
    )
    (net (code "55") (name "Net-(U5-BOOT)") (class "Default")
      (node (ref "Cboot5") (pin "1") (pinfunction "1_1") (pintype "passive"))
      (node (ref "U5") (pin "1") (pinfunction "BOOT_1") (pintype "passive"))
    )
    (net (code "56") (name "Net-(U5-COMP)") (class "Default")
      (node (ref "CcompB5") (pin "2") (pinfunction "2_2") (pintype "passive"))
      (node (ref "Rcomp5") (pin "1") (pinfunction "1_1") (pintype "passive"))
      (node (ref "U5") (pin "8") (pinfunction "COMP_8") (pintype "passive"))
    )
    (net (code "57") (name "Net-(U5-EN)") (class "Default")
      (node (ref "RenB5") (pin "2") (pinfunction "2_2") (pintype "passive"))
      (node (ref "RenT5") (pin "1") (pinfunction "1_1") (pintype "passive"))
      (node (ref "U5") (pin "3") (pinfunction "EN_3") (pintype "passive"))
    )
    (net (code "58") (name "Net-(U5-RT)") (class "Default")
      (node (ref "Rt5") (pin "2") (pinfunction "2_2") (pintype "passive"))
      (node (ref "U5") (pin "5") (pinfunction "RT_5") (pintype "passive"))
    )
    (net (code "59") (name "Net-(U5-SS)") (class "Default")
      (node (ref "Css5") (pin "2") (pinfunction "2_2") (pintype "passive"))
      (node (ref "U5") (pin "4") (pinfunction "SS_4") (pintype "passive"))
    )
    (net (code "60") (name "Net-(U5-VSENSE)") (class "Default")
      (node (ref "Rfbb5") (pin "2") (pinfunction "2_2") (pintype "passive"))
      (node (ref "Rfbt5") (pin "1") (pinfunction "1_1") (pintype "passive"))
      (node (ref "U5") (pin "7") (pinfunction "VSENSE_7") (pintype "passive"))
    )
    (net (code "61") (name "Net-(U5FPGA-BOOT)") (class "Default")
      (node (ref "Cboot5F") (pin "1") (pinfunction "1_1") (pintype "passive"))
      (node (ref "U5FPGA") (pin "1") (pinfunction "BOOT_1") (pintype "passive"))
    )
    (net (code "62") (name "Net-(U5FPGA-COMP)") (class "Default")
      (node (ref "CcompB5F") (pin "2") (pinfunction "2_2") (pintype "passive"))
      (node (ref "Rcomp5F") (pin "1") (pinfunction "1_1") (pintype "passive"))
      (node (ref "U5FPGA") (pin "8") (pinfunction "COMP_8") (pintype "passive"))
    )
    (net (code "63") (name "Net-(U5FPGA-EN)") (class "Default")
      (node (ref "RenB5F") (pin "2") (pinfunction "2_2") (pintype "passive"))
      (node (ref "RenT5F") (pin "1") (pinfunction "1_1") (pintype "passive"))
      (node (ref "U5FPGA") (pin "3") (pinfunction "EN_3") (pintype "passive"))
    )
    (net (code "64") (name "Net-(U5FPGA-RT)") (class "Default")
      (node (ref "Rt5F") (pin "2") (pinfunction "2_2") (pintype "passive"))
      (node (ref "U5FPGA") (pin "5") (pinfunction "RT_5") (pintype "passive"))
    )
    (net (code "65") (name "Net-(U5FPGA-SS)") (class "Default")
      (node (ref "Css5F") (pin "2") (pinfunction "2_2") (pintype "passive"))
      (node (ref "U5FPGA") (pin "4") (pinfunction "SS_4") (pintype "passive"))
    )
    (net (code "66") (name "Net-(U5FPGA-VSENSE)") (class "Default")
      (node (ref "Rfbb5F") (pin "2") (pinfunction "2_2") (pintype "passive"))
      (node (ref "Rfbt5F") (pin "1") (pinfunction "1_1") (pintype "passive"))
      (node (ref "U5FPGA") (pin "7") (pinfunction "VSENSE_7") (pintype "passive"))
    )
    (net (code "67") (name "VCC") (class "Default")
      (node (ref "BTN7971B1") (pin "7") (pinfunction "VS_7") (pintype "power_in"))
      (node (ref "BTN7971B2") (pin "7") (pinfunction "VS_7") (pintype "power_in"))
      (node (ref "Cin3") (pin "2") (pinfunction "2_2") (pintype "passive"))
      (node (ref "Cin5") (pin "2") (pinfunction "2_2") (pintype "passive"))
      (node (ref "Cin5F") (pin "2") (pinfunction "2_2") (pintype "passive"))
      (node (ref "P_PWR") (pin "1") (pinfunction "1_1") (pintype "passive"))
      (node (ref "RenT3") (pin "2") (pinfunction "2_2") (pintype "passive"))
      (node (ref "RenT5") (pin "2") (pinfunction "2_2") (pintype "passive"))
      (node (ref "RenT5F") (pin "2") (pinfunction "2_2") (pintype "passive"))
      (node (ref "U3") (pin "2") (pinfunction "VIN_2") (pintype "passive"))
      (node (ref "U5") (pin "2") (pinfunction "VIN_2") (pintype "passive"))
      (node (ref "U5FPGA") (pin "2") (pinfunction "VIN_2") (pintype "passive"))
    )
    (net (code "68") (name "unconnected-(U3-PWRGD-Pad6)") (class "Default")
      (node (ref "U3") (pin "6") (pinfunction "PWRGD_6") (pintype "passive"))
    )
    (net (code "69") (name "unconnected-(U5-PWRGD-Pad6)") (class "Default")
      (node (ref "U5") (pin "6") (pinfunction "PWRGD_6") (pintype "passive"))
    )
    (net (code "70") (name "unconnected-(U5FPGA-PWRGD-Pad6)") (class "Default")
      (node (ref "U5FPGA") (pin "6") (pinfunction "PWRGD_6") (pintype "passive"))
    )
  )
)
